# Encodeurs_Schematic.net
KiCad netlist of a schematic drawn in Altium Designer
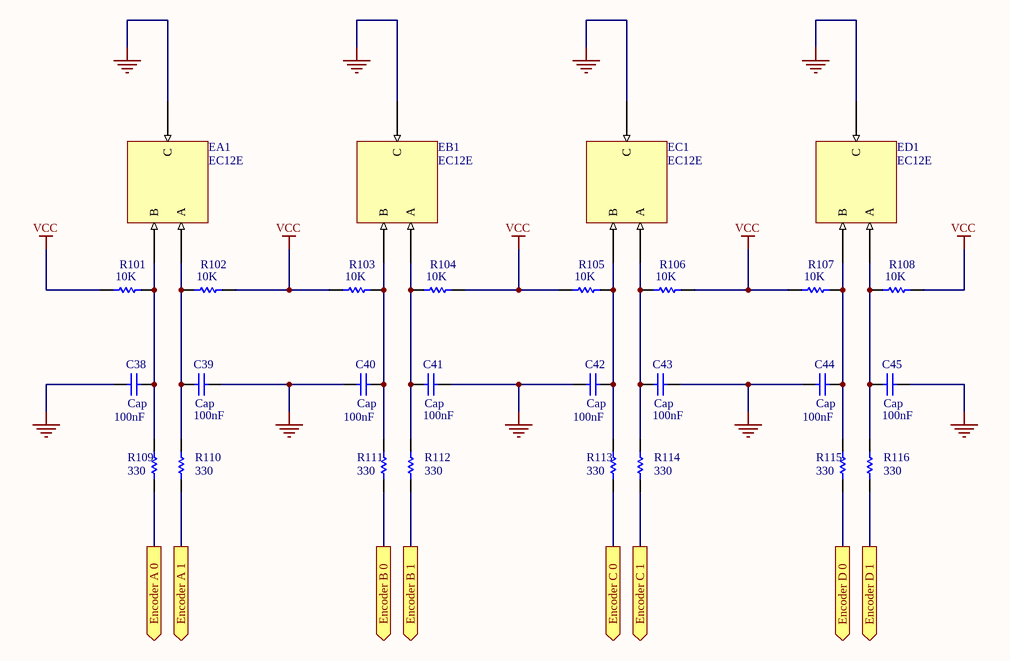
[diagram p0: Encodeurs.Schematic.SchDoc]

(export (version "E")
  (design (tool "Eeschema 10.0.6"))
  (components
    (comp (ref "C38")
      (value "Cap")
      (footprint "CAPC1608N")
      (description "Capacitor")
      (fields (field (name "ALTIUM_VALUE") "100nF") (field (name "PUBLISHER") "Altium Limited"))
      (libsource (lib "Miscellaneous Devices") (part "Cap"))
    )
    (comp (ref "C39")
      (value "Cap")
      (footprint "CAPC1608N")
      (description "Capacitor")
      (fields (field (name "ALTIUM_VALUE") "100nF") (field (name "PUBLISHER") "Altium Limited"))
      (libsource (lib "Miscellaneous Devices") (part "Cap"))
    )
    (comp (ref "C40")
      (value "Cap")
      (footprint "CAPC1608N")
      (description "Capacitor")
      (fields (field (name "ALTIUM_VALUE") "100nF") (field (name "PUBLISHER") "Altium Limited"))
      (libsource (lib "Miscellaneous Devices") (part "Cap"))
    )
    (comp (ref "C41")
      (value "Cap")
      (footprint "CAPC1608N")
      (description "Capacitor")
      (fields (field (name "ALTIUM_VALUE") "100nF") (field (name "PUBLISHER") "Altium Limited"))
      (libsource (lib "Miscellaneous Devices") (part "Cap"))
    )
    (comp (ref "C42")
      (value "Cap")
      (footprint "CAPC1608N")
      (description "Capacitor")
      (fields (field (name "ALTIUM_VALUE") "100nF") (field (name "PUBLISHER") "Altium Limited"))
      (libsource (lib "Miscellaneous Devices") (part "Cap"))
    )
    (comp (ref "C43")
      (value "Cap")
      (footprint "CAPC1608N")
      (description "Capacitor")
      (fields (field (name "ALTIUM_VALUE") "100nF") (field (name "PUBLISHER") "Altium Limited"))
      (libsource (lib "Miscellaneous Devices") (part "Cap"))
    )
    (comp (ref "C44")
      (value "Cap")
      (footprint "CAPC1608N")
      (description "Capacitor")
      (fields (field (name "ALTIUM_VALUE") "100nF") (field (name "PUBLISHER") "Altium Limited"))
      (libsource (lib "Miscellaneous Devices") (part "Cap"))
    )
    (comp (ref "C45")
      (value "Cap")
      (footprint "CAPC1608N")
      (description "Capacitor")
      (fields (field (name "ALTIUM_VALUE") "100nF") (field (name "PUBLISHER") "Altium Limited"))
      (libsource (lib "Miscellaneous Devices") (part "Cap"))
    )
    (comp (ref "EA1")
      (value "EC12E")
      (footprint "EC12E")
      (libsource (lib "SynthyTwo.Components") (part "EC12E"))
    )
    (comp (ref "EB1")
      (value "EC12E")
      (footprint "EC12E")
      (libsource (lib "SynthyTwo.Components") (part "EC12E"))
    )
    (comp (ref "EC1")
      (value "EC12E")
      (footprint "EC12E")
      (libsource (lib "SynthyTwo.Components") (part "EC12E"))
    )
    (comp (ref "ED1")
      (value "EC12E")
      (footprint "EC12E")
      (libsource (lib "SynthyTwo.Components") (part "EC12E"))
    )
    (comp (ref "R101")
      (value "10K")
      (footprint "CAPC1608N")
      (description "Resistor")
      (fields (field (name "PUBLISHER") "Altium Limited"))
      (libsource (lib "Miscellaneous Devices") (part "Res1"))
    )
    (comp (ref "R102")
      (value "10K")
      (footprint "CAPC1608N")
      (description "Resistor")
      (fields (field (name "PUBLISHER") "Altium Limited"))
      (libsource (lib "Miscellaneous Devices") (part "Res1"))
    )
    (comp (ref "R103")
      (value "10K")
      (footprint "CAPC1608N")
      (description "Resistor")
      (fields (field (name "PUBLISHER") "Altium Limited"))
      (libsource (lib "Miscellaneous Devices") (part "Res1"))
    )
    (comp (ref "R104")
      (value "10K")
      (footprint "CAPC1608N")
      (description "Resistor")
      (fields (field (name "PUBLISHER") "Altium Limited"))
      (libsource (lib "Miscellaneous Devices") (part "Res1"))
    )
    (comp (ref "R105")
      (value "10K")
      (footprint "CAPC1608N")
      (description "Resistor")
      (fields (field (name "PUBLISHER") "Altium Limited"))
      (libsource (lib "Miscellaneous Devices") (part "Res1"))
    )
    (comp (ref "R106")
      (value "10K")
      (footprint "CAPC1608N")
      (description "Resistor")
      (fields (field (name "PUBLISHER") "Altium Limited"))
      (libsource (lib "Miscellaneous Devices") (part "Res1"))
    )
    (comp (ref "R107")
      (value "10K")
      (footprint "CAPC1608N")
      (description "Resistor")
      (fields (field (name "PUBLISHER") "Altium Limited"))
      (libsource (lib "Miscellaneous Devices") (part "Res1"))
    )
    (comp (ref "R108")
      (value "10K")
      (footprint "CAPC1608N")
      (description "Resistor")
      (fields (field (name "PUBLISHER") "Altium Limited"))
      (libsource (lib "Miscellaneous Devices") (part "Res1"))
    )
    (comp (ref "R109")
      (value "330")
      (footprint "CAPC1608N")
      (description "Resistor")
      (fields (field (name "PUBLISHER") "Altium Limited"))
      (libsource (lib "Miscellaneous Devices") (part "Res1"))
    )
    (comp (ref "R110")
      (value "330")
      (footprint "CAPC1608N")
      (description "Resistor")
      (fields (field (name "PUBLISHER") "Altium Limited"))
      (libsource (lib "Miscellaneous Devices") (part "Res1"))
    )
    (comp (ref "R111")
      (value "330")
      (footprint "CAPC1608N")
      (description "Resistor")
      (fields (field (name "PUBLISHER") "Altium Limited"))
      (libsource (lib "Miscellaneous Devices") (part "Res1"))
    )
    (comp (ref "R112")
      (value "330")
      (footprint "CAPC1608N")
      (description "Resistor")
      (fields (field (name "PUBLISHER") "Altium Limited"))
      (libsource (lib "Miscellaneous Devices") (part "Res1"))
    )
    (comp (ref "R113")
      (value "330")
      (footprint "CAPC1608N")
      (description "Resistor")
      (fields (field (name "PUBLISHER") "Altium Limited"))
      (libsource (lib "Miscellaneous Devices") (part "Res1"))
    )
    (comp (ref "R114")
      (value "330")
      (footprint "CAPC1608N")
      (description "Resistor")
      (fields (field (name "PUBLISHER") "Altium Limited"))
      (libsource (lib "Miscellaneous Devices") (part "Res1"))
    )
    (comp (ref "R115")
      (value "330")
      (footprint "CAPC1608N")
      (description "Resistor")
      (fields (field (name "PUBLISHER") "Altium Limited"))
      (libsource (lib "Miscellaneous Devices") (part "Res1"))
    )
    (comp (ref "R116")
      (value "330")
      (footprint "CAPC1608N")
      (description "Resistor")
      (fields (field (name "PUBLISHER") "Altium Limited"))
      (libsource (lib "Miscellaneous Devices") (part "Res1"))
    )
  )
  (nets
    (net (code "1") (name "/Encoder A 0") (class "Default")
      (node (ref "R109") (pin "1") (pinfunction "1_1") (pintype "passive"))
    )
    (net (code "2") (name "/Encoder A 1") (class "Default")
      (node (ref "R110") (pin "1") (pinfunction "1_1") (pintype "passive"))
    )
    (net (code "3") (name "/Encoder B 0") (class "Default")
      (node (ref "R111") (pin "1") (pinfunction "1_1") (pintype "passive"))
    )
    (net (code "4") (name "/Encoder B 1") (class "Default")
      (node (ref "R112") (pin "1") (pinfunction "1_1") (pintype "passive"))
    )
    (net (code "5") (name "/Encoder C 0") (class "Default")
      (node (ref "R113") (pin "1") (pinfunction "1_1") (pintype "passive"))
    )
    (net (code "6") (name "/Encoder C 1") (class "Default")
      (node (ref "R114") (pin "1") (pinfunction "1_1") (pintype "passive"))
    )
    (net (code "7") (name "/Encoder D 0") (class "Default")
      (node (ref "R115") (pin "1") (pinfunction "1_1") (pintype "passive"))
    )
    (net (code "8") (name "/Encoder D 1") (class "Default")
      (node (ref "R116") (pin "1") (pinfunction "1_1") (pintype "passive"))
    )
    (net (code "9") (name "GND") (class "Default")
      (node (ref "C38") (pin "1") (pinfunction "1_1") (pintype "passive"))
      (node (ref "C39") (pin "1") (pinfunction "1_1") (pintype "passive"))
      (node (ref "C40") (pin "1") (pinfunction "1_1") (pintype "passive"))
      (node (ref "C41") (pin "1") (pinfunction "1_1") (pintype "passive"))
      (node (ref "C42") (pin "1") (pinfunction "1_1") (pintype "passive"))
      (node (ref "C43") (pin "1") (pinfunction "1_1") (pintype "passive"))
      (node (ref "C44") (pin "1") (pinfunction "1_1") (pintype "passive"))
      (node (ref "C45") (pin "1") (pinfunction "1_1") (pintype "passive"))
      (node (ref "EA1") (pin "3") (pinfunction "C_3") (pintype "input"))
      (node (ref "EB1") (pin "3") (pinfunction "C_3") (pintype "input"))
      (node (ref "EC1") (pin "3") (pinfunction "C_3") (pintype "input"))
      (node (ref "ED1") (pin "3") (pinfunction "C_3") (pintype "input"))
    )
    (net (code "10") (name "Net-(EA1-A)") (class "Default")
      (node (ref "C39") (pin "2") (pinfunction "2_2") (pintype "passive"))
      (node (ref "EA1") (pin "1") (pinfunction "A_1") (pintype "input"))
      (node (ref "R102") (pin "1") (pinfunction "1_1") (pintype "passive"))
      (node (ref "R110") (pin "2") (pinfunction "2_2") (pintype "passive"))
    )
    (net (code "11") (name "Net-(EA1-B)") (class "Default")
      (node (ref "C38") (pin "2") (pinfunction "2_2") (pintype "passive"))
      (node (ref "EA1") (pin "2") (pinfunction "B_2") (pintype "input"))
      (node (ref "R101") (pin "2") (pinfunction "2_2") (pintype "passive"))
      (node (ref "R109") (pin "2") (pinfunction "2_2") (pintype "passive"))
    )
    (net (code "12") (name "Net-(EB1-A)") (class "Default")
      (node (ref "C41") (pin "2") (pinfunction "2_2") (pintype "passive"))
      (node (ref "EB1") (pin "1") (pinfunction "A_1") (pintype "input"))
      (node (ref "R104") (pin "1") (pinfunction "1_1") (pintype "passive"))
      (node (ref "R112") (pin "2") (pinfunction "2_2") (pintype "passive"))
    )
    (net (code "13") (name "Net-(EB1-B)") (class "Default")
      (node (ref "C40") (pin "2") (pinfunction "2_2") (pintype "passive"))
      (node (ref "EB1") (pin "2") (pinfunction "B_2") (pintype "input"))
      (node (ref "R103") (pin "2") (pinfunction "2_2") (pintype "passive"))
      (node (ref "R111") (pin "2") (pinfunction "2_2") (pintype "passive"))
    )
    (net (code "14") (name "Net-(EC1-A)") (class "Default")
      (node (ref "C43") (pin "2") (pinfunction "2_2") (pintype "passive"))
      (node (ref "EC1") (pin "1") (pinfunction "A_1") (pintype "input"))
      (node (ref "R106") (pin "1") (pinfunction "1_1") (pintype "passive"))
      (node (ref "R114") (pin "2") (pinfunction "2_2") (pintype "passive"))
    )
    (net (code "15") (name "Net-(EC1-B)") (class "Default")
      (node (ref "C42") (pin "2") (pinfunction "2_2") (pintype "passive"))
      (node (ref "EC1") (pin "2") (pinfunction "B_2") (pintype "input"))
      (node (ref "R105") (pin "2") (pinfunction "2_2") (pintype "passive"))
      (node (ref "R113") (pin "2") (pinfunction "2_2") (pintype "passive"))
    )
    (net (code "16") (name "Net-(ED1-A)") (class "Default")
      (node (ref "C45") (pin "2") (pinfunction "2_2") (pintype "passive"))
      (node (ref "ED1") (pin "1") (pinfunction "A_1") (pintype "input"))
      (node (ref "R108") (pin "1") (pinfunction "1_1") (pintype "passive"))
      (node (ref "R116") (pin "2") (pinfunction "2_2") (pintype "passive"))
    )
    (net (code "17") (name "Net-(ED1-B)") (class "Default")
      (node (ref "C44") (pin "2") (pinfunction "2_2") (pintype "passive"))
      (node (ref "ED1") (pin "2") (pinfunction "B_2") (pintype "input"))
      (node (ref "R107") (pin "2") (pinfunction "2_2") (pintype "passive"))
      (node (ref "R115") (pin "2") (pinfunction "2_2") (pintype "passive"))
    )
    (net (code "18") (name "VCC") (class "Default")
      (node (ref "R101") (pin "1") (pinfunction "1_1") (pintype "passive"))
      (node (ref "R102") (pin "2") (pinfunction "2_2") (pintype "passive"))
      (node (ref "R103") (pin "1") (pinfunction "1_1") (pintype "passive"))
      (node (ref "R104") (pin "2") (pinfunction "2_2") (pintype "passive"))
      (node (ref "R105") (pin "1") (pinfunction "1_1") (pintype "passive"))
      (node (ref "R106") (pin "2") (pinfunction "2_2") (pintype "passive"))
      (node (ref "R107") (pin "1") (pinfunction "1_1") (pintype "passive"))
      (node (ref "R108") (pin "2") (pinfunction "2_2") (pintype "passive"))
    )
  )
)
